# UP_Aktor_1Wechsler_16A_V0_1.net
KiCad netlist of a schematic drawn in EAGLE
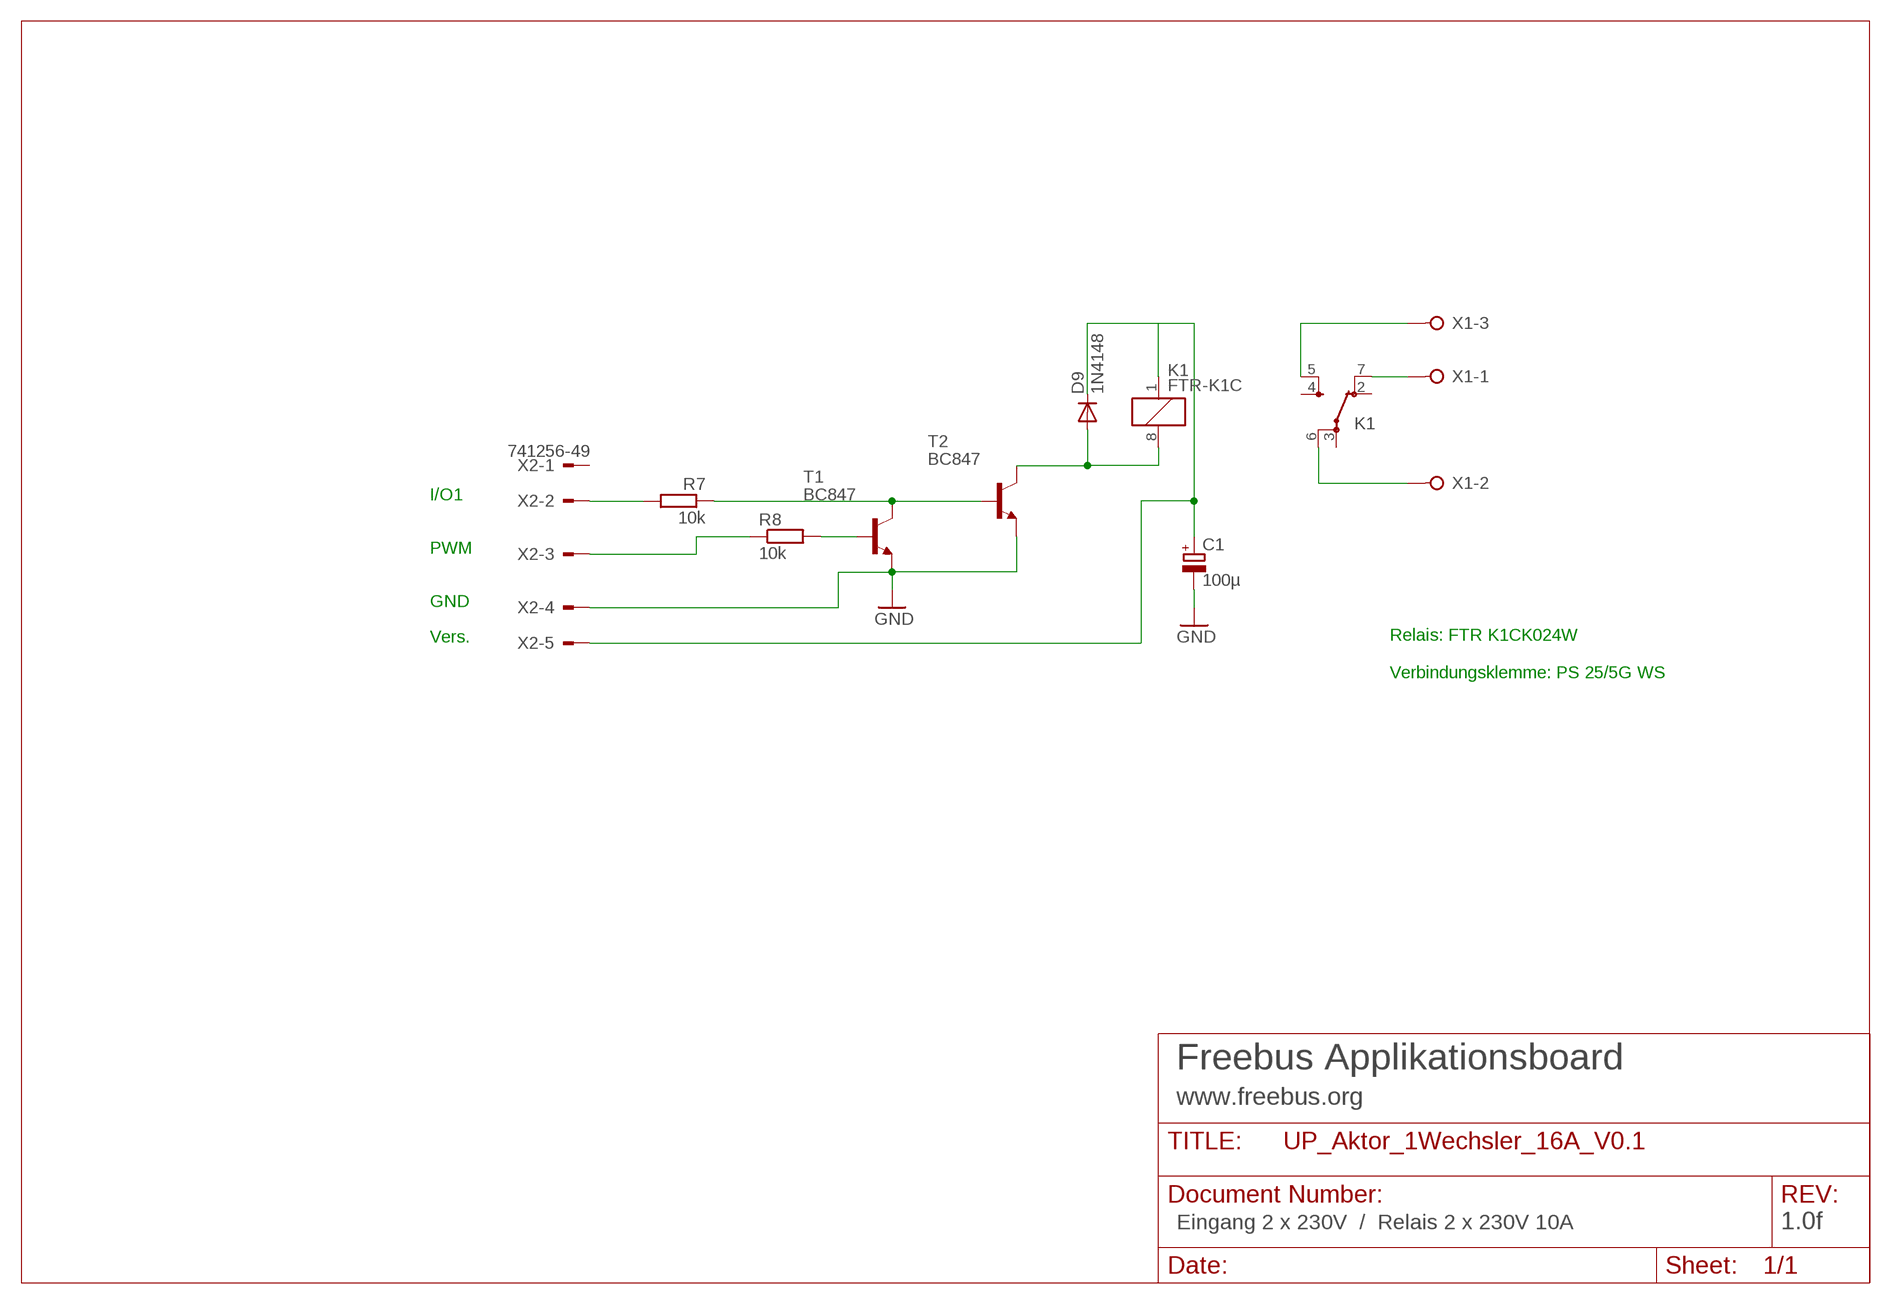
[diagram p0: schematic, sheet 1]

(export (version "E")
  (design (tool "Eeschema 10.0.6"))
  (components
    (comp (ref "C1")
      (value "100µ")
      (footprint "eagle-import:E3,5-8")
      (libsource (lib "eagle-import") (part "CPOL-EUE3.5-8"))
    )
    (comp (ref "D9")
      (value "1N4148")
      (footprint "eagle-import:MINIMELF")
      (libsource (lib "eagle-import") (part "DIODE-MINIMELF"))
    )
    (comp (ref "K1")
      (value "FTR-K1C")
      (footprint "eagle-import:FTR-K1C")
      (libsource (lib "eagle-import") (part "FTR-K1C"))
    )
    (comp (ref "R7")
      (value "10k")
      (footprint "eagle-import:M1206")
      (libsource (lib "eagle-import") (part "R-EU_M1206"))
    )
    (comp (ref "R8")
      (value "10k")
      (footprint "eagle-import:M1206")
      (libsource (lib "eagle-import") (part "R-EU_M1206"))
    )
    (comp (ref "T1")
      (value "BC847")
      (footprint "eagle-import:SOT23")
      (libsource (lib "eagle-import") (part "BC847"))
    )
    (comp (ref "T2")
      (value "BC847")
      (footprint "eagle-import:SOT23")
      (libsource (lib "eagle-import") (part "BC847"))
    )
    (comp (ref "X1")
      (value "W237-03P")
      (footprint "eagle-import:W237-133")
      (libsource (lib "eagle-import") (part "W237-03P"))
    )
    (comp (ref "X2")
      (value "741256-49")
      (footprint "eagle-import:741256-49")
      (libsource (lib "eagle-import") (part "741256-49"))
    )
  )
  (nets
    (net (code "1") (name "GND") (class "Default")
      (node (ref "C1") (pin "-") (pinfunction "-_-") (pintype "passive"))
      (node (ref "T1") (pin "2") (pinfunction "E_2") (pintype "passive"))
      (node (ref "T2") (pin "2") (pinfunction "E_2") (pintype "passive"))
      (node (ref "X2") (pin "4") (pinfunction "KL_4") (pintype "passive"))
    )
    (net (code "2") (name "Net-(K1A-OB)") (class "Default")
      (node (ref "K1") (pin "7") (pinfunction "OB_7") (pintype "passive"))
      (node (ref "X1") (pin "1") (pinfunction "KL_1") (pintype "passive"))
    )
    (net (code "3") (name "Net-(K1A-PB)") (class "Default")
      (node (ref "K1") (pin "6") (pinfunction "PB_6") (pintype "passive"))
      (node (ref "X1") (pin "2") (pinfunction "KL_2") (pintype "passive"))
    )
    (net (code "4") (name "Net-(K1A-SB)") (class "Default")
      (node (ref "K1") (pin "5") (pinfunction "SB_5") (pintype "passive"))
      (node (ref "X1") (pin "3") (pinfunction "KL_3") (pintype "passive"))
    )
    (net (code "5") (name "Net-(K1B-2)") (class "Default")
      (node (ref "D9") (pin "A") (pinfunction "A_A") (pintype "passive"))
      (node (ref "K1") (pin "8") (pinfunction "2_8") (pintype "passive"))
      (node (ref "T2") (pin "3") (pinfunction "C_3") (pintype "passive"))
    )
    (net (code "6") (name "Net-(T1-B)") (class "Default")
      (node (ref "R8") (pin "2") (pinfunction "2_2") (pintype "passive"))
      (node (ref "T1") (pin "1") (pinfunction "B_1") (pintype "passive"))
    )
    (net (code "7") (name "Net-(T1-C)") (class "Default")
      (node (ref "R7") (pin "1") (pinfunction "1_1") (pintype "passive"))
      (node (ref "T1") (pin "3") (pinfunction "C_3") (pintype "passive"))
      (node (ref "T2") (pin "1") (pinfunction "B_1") (pintype "passive"))
    )
    (net (code "8") (name "Net-(X2B-KL)") (class "Default")
      (node (ref "R7") (pin "2") (pinfunction "2_2") (pintype "passive"))
      (node (ref "X2") (pin "2") (pinfunction "KL_2") (pintype "passive"))
    )
    (net (code "9") (name "Net-(X2C-KL)") (class "Default")
      (node (ref "R8") (pin "1") (pinfunction "1_1") (pintype "passive"))
      (node (ref "X2") (pin "3") (pinfunction "KL_3") (pintype "passive"))
    )
    (net (code "10") (name "Net-(X2E-KL)") (class "Default")
      (node (ref "C1") (pin "+") (pinfunction "+_+") (pintype "passive"))
      (node (ref "D9") (pin "C") (pinfunction "C_C") (pintype "passive"))
      (node (ref "K1") (pin "1") (pinfunction "1_1") (pintype "passive"))
      (node (ref "X2") (pin "5") (pinfunction "KL_5") (pintype "passive"))
    )
    (net (code "11") (name "unconnected-(K1A-OA-Pad2)") (class "Default")
      (node (ref "K1") (pin "2") (pinfunction "OA_2") (pintype "passive"))
    )
    (net (code "12") (name "unconnected-(K1A-PA-Pad3)") (class "Default")
      (node (ref "K1") (pin "3") (pinfunction "PA_3") (pintype "passive"))
    )
    (net (code "13") (name "unconnected-(K1A-SA-Pad4)") (class "Default")
      (node (ref "K1") (pin "4") (pinfunction "SA_4") (pintype "passive"))
    )
    (net (code "14") (name "unconnected-(X2A-KL-Pad1)") (class "Default")
      (node (ref "X2") (pin "1") (pinfunction "KL_1") (pintype "passive"))
    )
  )
)
